# Peripherals.net
KiCad netlist of a schematic drawn in Altium Designer
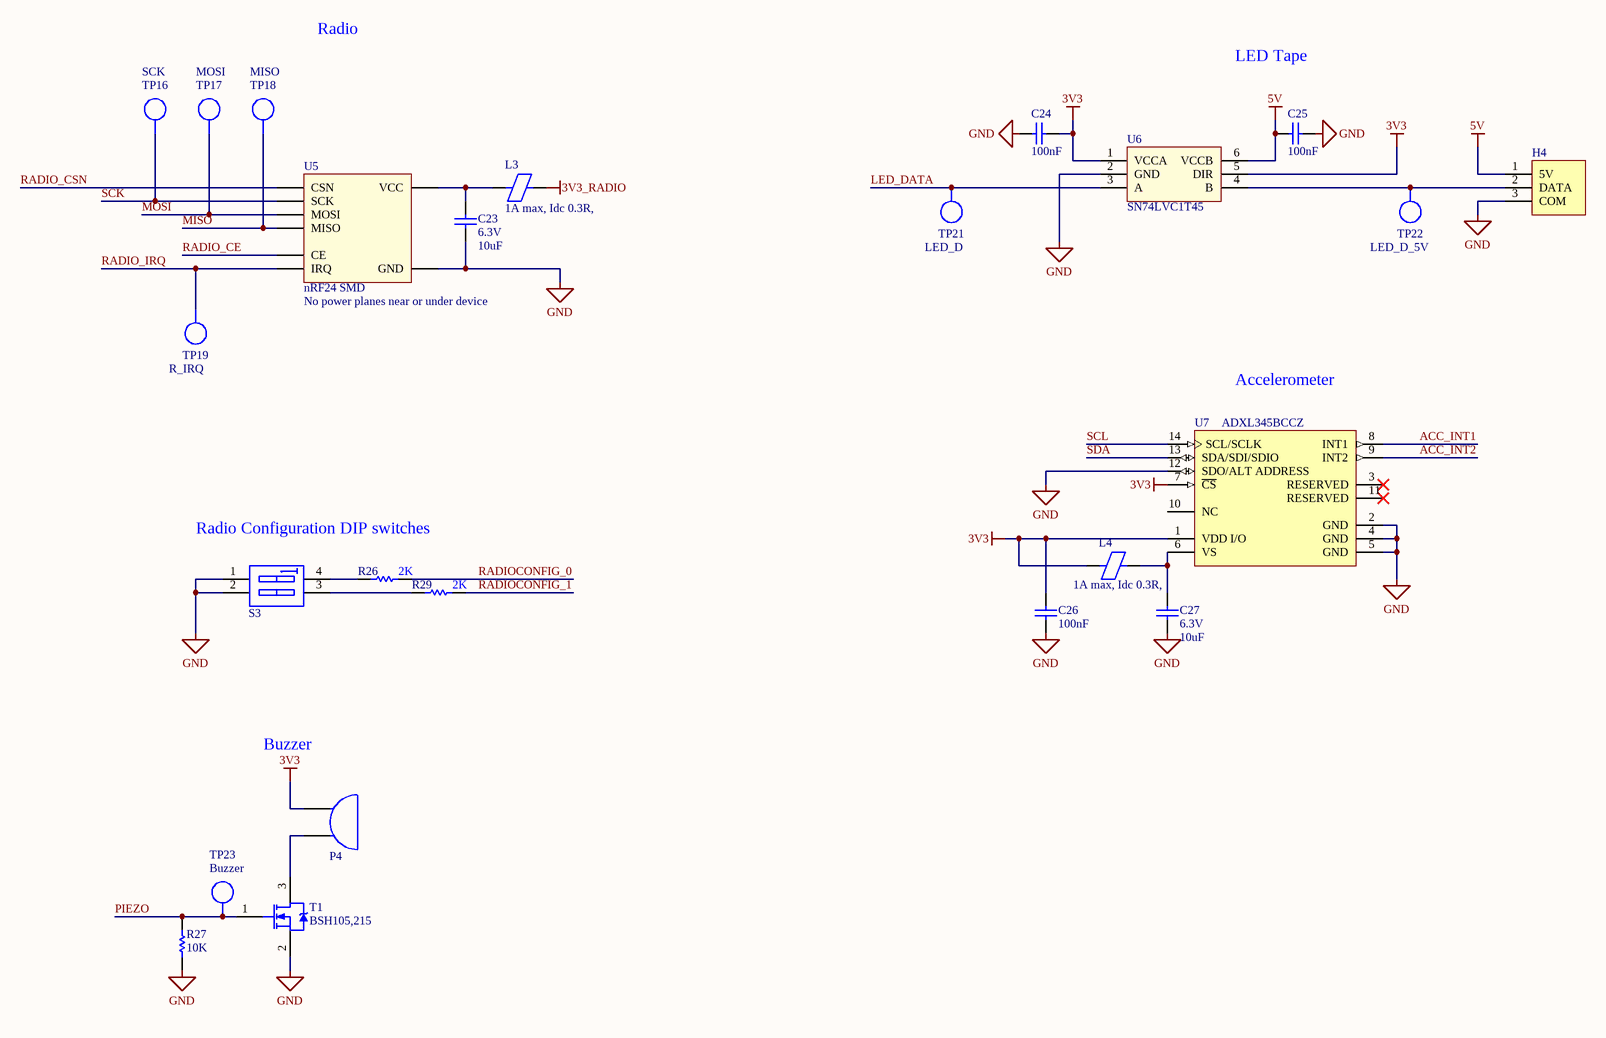
[diagram p0: Peripherals.SchDoc]

(export (version "E")
  (design (tool "Eeschema 10.0.6"))
  (components
    (comp (ref "C23")
      (value "10uF")
      (footprint "CAPC1608L")
      (description "CAP CER 10UF X5R +-20% 6V3 0603")
      (fields (field (name "VOLTAGE - RATED") "6.3V"))
      (libsource (lib "ECE_ComponentsAD23") (part "CC_10uF_0603"))
    )
    (comp (ref "C24")
      (value "100nF")
      (footprint "CAPC1608L")
      (description "CAP CER 100nF X7R +-10% 50V 0603")
      (libsource (lib "ECE_ComponentsAD23") (part "CC_100nF_0603"))
    )
    (comp (ref "C25")
      (value "100nF")
      (footprint "CAPC1608L")
      (description "CAP CER 100nF X7R +-10% 50V 0603")
      (libsource (lib "ECE_ComponentsAD23") (part "CC_100nF_0603"))
    )
    (comp (ref "C26")
      (value "100nF")
      (footprint "CAPC1608L")
      (description "CAP CER 100nF X7R +-10% 50V 0603")
      (libsource (lib "ECE_ComponentsAD23") (part "CC_100nF_0603"))
    )
    (comp (ref "C27")
      (value "10uF")
      (footprint "CAPC1608L")
      (description "CAP CER 10UF X5R +-20% 6V3 0603")
      (fields (field (name "VOLTAGE - RATED") "6.3V"))
      (libsource (lib "ECE_ComponentsAD23") (part "CC_10uF_0603"))
    )
    (comp (ref "H4")
      (value "3 Pin Molex KK Hdr")
      (footprint "MOLEX_KK_3_HDR")
      (description "CONN HEADER 3POS 2.54mm VERT_Thru Hole")
      (fields (field (name "MANUFACTURER") "Molex"))
      (libsource (lib "ENCE461AD23") (part "LED_Strip_Header"))
    )
    (comp (ref "L3")
      (value "1A max, Idc 0.3R,")
      (footprint "INDC3216L")
      (description "Ferrite Bead, Rdc 0.3R, Z100MHZ 600R, Imax 1A, SMD 1206")
      (fields
        (field (name "MANUFACTURER") "FAIR-RITE")
        (field (name "MANUFACTURER PART NUMBER") "2512066017Y1")
      )
      (libsource (lib "ECE_ComponentsAD23") (part "IN_Ferrite-Bead"))
    )
    (comp (ref "L4")
      (value "1A max, Idc 0.3R,")
      (footprint "INDC3216L")
      (description "Ferrite Bead, Rdc 0.3R, Z100MHZ 600R, Imax 1A, SMD 1206")
      (fields
        (field (name "MANUFACTURER") "FAIR-RITE")
        (field (name "MANUFACTURER PART NUMBER") "2512066017Y1")
      )
      (libsource (lib "ECE_ComponentsAD23") (part "IN_Ferrite-Bead"))
    )
    (comp (ref "P4")
      (value "Piezo Buzzer")
      (footprint "BUZZER")
      (description "TDK - PS1240P02BT - BUZZER, PIEZO, 70DB, 12.2MM")
      (libsource (lib "ENCE461AD23") (part "Piezo Buzzer"))
    )
    (comp (ref "R26")
      (value "2K")
      (footprint "RESC1608L")
      (description "RES 2K OHM 1/10W 5% 0603 SMD")
      (libsource (lib "ECE_ComponentsAD23") (part "RS_2K"))
    )
    (comp (ref "R27")
      (value "10K")
      (footprint "RESC1608L")
      (description "RES 10.0K OHM 1/10W 5% 0603 SMD")
      (libsource (lib "ECE_ComponentsAD23") (part "RS_10K"))
    )
    (comp (ref "R29")
      (value "2K")
      (footprint "RESC1608L")
      (description "RES 2K OHM 1/10W 5% 0603 SMD")
      (libsource (lib "ECE_ComponentsAD23") (part "RS_2K"))
    )
    (comp (ref "S3")
      (value "WS_SW DIP-2")
      (footprint "DIP_SW_2WAY_SMD")
      (description "DIP Switch, 2 Position, SPST SMD")
      (fields
        (field (name "MANUFACTURER") "OMRON ELECTRONIC COMPONENTS")
        (field (name "MANUFACTURER PART NUMBER") "A6SN-2101")
      )
      (libsource (lib "ECE_ComponentsAD23") (part "WS_SW DIP-2"))
    )
    (comp (ref "T1")
      (value "BSH105,215")
      (footprint "SOT23_L")
      (description "MOSFET N-CH 20V 1.05A SOT-23")
      (fields
        (field (name "MANUFACTURER") "NXP Semiconductors")
        (field (name "MANUFACTURER PART NUMBER") "BSH105,215")
      )
      (libsource (lib "ECE_ComponentsAD23") (part "TM_BSH105"))
    )
    (comp (ref "TP16")
      (value "SCK")
      (footprint "TP_1206")
      (description "Test-Point 3.3x1.6x2.1mm SMD")
      (fields
        (field (name "MANUFACTURER") "Harwin Inc")
        (field (name "MANUFACTURER PART NUMBER") "S1751-46R")
      )
      (libsource (lib "ECE_ComponentsAD23") (part "TP_1206"))
    )
    (comp (ref "TP17")
      (value "MOSI")
      (footprint "TP_1206")
      (description "Test-Point 3.3x1.6x2.1mm SMD")
      (fields
        (field (name "MANUFACTURER") "Harwin Inc")
        (field (name "MANUFACTURER PART NUMBER") "S1751-46R")
      )
      (libsource (lib "ECE_ComponentsAD23") (part "TP_1206"))
    )
    (comp (ref "TP18")
      (value "MISO")
      (footprint "TP_1206")
      (description "Test-Point 3.3x1.6x2.1mm SMD")
      (fields
        (field (name "MANUFACTURER") "Harwin Inc")
        (field (name "MANUFACTURER PART NUMBER") "S1751-46R")
      )
      (libsource (lib "ECE_ComponentsAD23") (part "TP_1206"))
    )
    (comp (ref "TP19")
      (value "R_IRQ")
      (footprint "TP_1206")
      (description "Test-Point 3.3x1.6x2.1mm SMD")
      (fields
        (field (name "MANUFACTURER") "Harwin Inc")
        (field (name "MANUFACTURER PART NUMBER") "S1751-46R")
      )
      (libsource (lib "ECE_ComponentsAD23") (part "TP_1206"))
    )
    (comp (ref "TP21")
      (value "LED_D")
      (footprint "TP_1206")
      (description "Test-Point 3.3x1.6x2.1mm SMD")
      (fields
        (field (name "MANUFACTURER") "Harwin Inc")
        (field (name "MANUFACTURER PART NUMBER") "S1751-46R")
      )
      (libsource (lib "ECE_ComponentsAD23") (part "TP_1206"))
    )
    (comp (ref "TP22")
      (value "LED_D_5V")
      (footprint "TP_1206")
      (description "Test-Point 3.3x1.6x2.1mm SMD")
      (fields
        (field (name "MANUFACTURER") "Harwin Inc")
        (field (name "MANUFACTURER PART NUMBER") "S1751-46R")
      )
      (libsource (lib "ECE_ComponentsAD23") (part "TP_1206"))
    )
    (comp (ref "TP23")
      (value "Buzzer")
      (footprint "TP_1206")
      (description "Test-Point 3.3x1.6x2.1mm SMD")
      (fields
        (field (name "MANUFACTURER") "Harwin Inc")
        (field (name "MANUFACTURER PART NUMBER") "S1751-46R")
      )
      (libsource (lib "ECE_ComponentsAD23") (part "TP_1206"))
    )
    (comp (ref "U5")
      (value "nRF24 SMD")
      (footprint "NRF24")
      (description "nRF24 SMD Module")
      (fields (field (name "WARNING") "No power planes near or under device"))
      (libsource (lib "ENCE461AD23") (part "NRF24"))
    )
    (comp (ref "U6")
      (value "SN74LVC1T45")
      (footprint "SOT23-6_N")
      (description "1.8V - 5V level converter")
      (libsource (lib "ENCE461AD23") (part "SN74LVC1T45"))
    )
    (comp (ref "U7")
      (value "ADXL345BCCZ")
      (footprint "ADI-CC-14-1_V")
      (fields (field (name "MANUFACTURER") "Analog Devices"))
      (libsource (lib "ENCE461AD23") (part "ADXL345BCCZ"))
    )
  )
  (nets
    (net (code "1") (name "/ACC_INT1") (class "Default")
      (node (ref "U7") (pin "8") (pinfunction "INT1_8") (pintype "output"))
    )
    (net (code "2") (name "/ACC_INT2") (class "Default")
      (node (ref "U7") (pin "9") (pinfunction "INT2_9") (pintype "output"))
    )
    (net (code "3") (name "/LED_DATA") (class "Default")
      (node (ref "TP21") (pin "1") (pinfunction "1_1") (pintype "passive"))
      (node (ref "U6") (pin "3") (pinfunction "A_3") (pintype "passive"))
    )
    (net (code "4") (name "/MISO") (class "Default")
      (node (ref "TP18") (pin "1") (pinfunction "1_1") (pintype "passive"))
      (node (ref "U5") (pin "7") (pinfunction "MISO_7") (pintype "passive"))
    )
    (net (code "5") (name "/MOSI") (class "Default")
      (node (ref "TP17") (pin "1") (pinfunction "1_1") (pintype "passive"))
      (node (ref "U5") (pin "6") (pinfunction "MOSI_6") (pintype "passive"))
    )
    (net (code "6") (name "/PIEZO") (class "Default")
      (node (ref "R27") (pin "1") (pinfunction "1_1") (pintype "passive"))
      (node (ref "T1") (pin "1") (pinfunction "1_1") (pintype "passive"))
      (node (ref "TP23") (pin "1") (pinfunction "1_1") (pintype "passive"))
    )
    (net (code "7") (name "/RADIOCONFIG_0") (class "Default")
      (node (ref "R26") (pin "2") (pinfunction "2_2") (pintype "passive"))
    )
    (net (code "8") (name "/RADIOCONFIG_1") (class "Default")
      (node (ref "R29") (pin "2") (pinfunction "2_2") (pintype "passive"))
    )
    (net (code "9") (name "/RADIO_CE") (class "Default")
      (node (ref "U5") (pin "3") (pinfunction "CE_3") (pintype "passive"))
    )
    (net (code "10") (name "/RADIO_CSN") (class "Default")
      (node (ref "U5") (pin "4") (pinfunction "CSN_4") (pintype "passive"))
    )
    (net (code "11") (name "/RADIO_IRQ") (class "Default")
      (node (ref "TP19") (pin "1") (pinfunction "1_1") (pintype "passive"))
      (node (ref "U5") (pin "8") (pinfunction "IRQ_8") (pintype "passive"))
    )
    (net (code "12") (name "/SCK") (class "Default")
      (node (ref "TP16") (pin "1") (pinfunction "1_1") (pintype "passive"))
      (node (ref "U5") (pin "5") (pinfunction "SCK_5") (pintype "passive"))
    )
    (net (code "13") (name "/SCL") (class "Default")
      (node (ref "U7") (pin "14") (pinfunction "SCL/SCLK_14") (pintype "input"))
    )
    (net (code "14") (name "/SDA") (class "Default")
      (node (ref "U7") (pin "13") (pinfunction "SDA/SDI/SDIO_13") (pintype "bidirectional"))
    )
    (net (code "15") (name "3V3") (class "Default")
      (node (ref "C24") (pin "2") (pinfunction "2_2") (pintype "passive"))
      (node (ref "C26") (pin "2") (pinfunction "2_2") (pintype "passive"))
      (node (ref "L4") (pin "2") (pinfunction "2_2") (pintype "passive"))
      (node (ref "P4") (pin "1") (pinfunction "1_1") (pintype "passive"))
      (node (ref "U6") (pin "1") (pinfunction "VCCA_1") (pintype "passive"))
      (node (ref "U6") (pin "5") (pinfunction "DIR_5") (pintype "passive"))
      (node (ref "U7") (pin "1") (pinfunction "VDD_I/O_1") (pintype "power_in"))
      (node (ref "U7") (pin "7") (pinfunction "~{CS}_7") (pintype "input"))
    )
    (net (code "16") (name "3V3_RADIO") (class "Default")
      (node (ref "L3") (pin "2") (pinfunction "2_2") (pintype "passive"))
    )
    (net (code "17") (name "5V") (class "Default")
      (node (ref "C25") (pin "2") (pinfunction "2_2") (pintype "passive"))
      (node (ref "H4") (pin "1") (pinfunction "5V_1") (pintype "passive"))
      (node (ref "U6") (pin "6") (pinfunction "VCCB_6") (pintype "passive"))
    )
    (net (code "18") (name "GND") (class "Default")
      (node (ref "C23") (pin "1") (pinfunction "1_1") (pintype "passive"))
      (node (ref "C24") (pin "1") (pinfunction "1_1") (pintype "passive"))
      (node (ref "C25") (pin "1") (pinfunction "1_1") (pintype "passive"))
      (node (ref "C26") (pin "1") (pinfunction "1_1") (pintype "passive"))
      (node (ref "C27") (pin "1") (pinfunction "1_1") (pintype "passive"))
      (node (ref "H4") (pin "3") (pinfunction "COM_3") (pintype "passive"))
      (node (ref "R27") (pin "2") (pinfunction "2_2") (pintype "passive"))
      (node (ref "S3") (pin "1") (pinfunction "A1_1") (pintype "passive"))
      (node (ref "S3") (pin "2") (pinfunction "A2_2") (pintype "passive"))
      (node (ref "T1") (pin "2") (pinfunction "2_2") (pintype "passive"))
      (node (ref "U5") (pin "2") (pinfunction "GND_2") (pintype "passive"))
      (node (ref "U6") (pin "2") (pinfunction "GND_2") (pintype "passive"))
      (node (ref "U7") (pin "12") (pinfunction "SDO/ALT_ADDRESS_12") (pintype "bidirectional"))
      (node (ref "U7") (pin "2") (pinfunction "GND_2") (pintype "power_in"))
      (node (ref "U7") (pin "4") (pinfunction "GND_4") (pintype "power_in"))
      (node (ref "U7") (pin "5") (pinfunction "GND_5") (pintype "power_in"))
    )
    (net (code "19") (name "Net-(H4-DATA)") (class "Default")
      (node (ref "H4") (pin "2") (pinfunction "DATA_2") (pintype "passive"))
      (node (ref "TP22") (pin "1") (pinfunction "1_1") (pintype "passive"))
      (node (ref "U6") (pin "4") (pinfunction "B_4") (pintype "passive"))
    )
    (net (code "20") (name "Net-(P4-Pad2)") (class "Default")
      (node (ref "P4") (pin "2") (pinfunction "2_2") (pintype "passive"))
      (node (ref "T1") (pin "3") (pinfunction "3_3") (pintype "passive"))
    )
    (net (code "21") (name "Net-(S3-B1)") (class "Default")
      (node (ref "R26") (pin "1") (pinfunction "1_1") (pintype "passive"))
      (node (ref "S3") (pin "4") (pinfunction "B1_4") (pintype "passive"))
    )
    (net (code "22") (name "Net-(S3-B2)") (class "Default")
      (node (ref "R29") (pin "1") (pinfunction "1_1") (pintype "passive"))
      (node (ref "S3") (pin "3") (pinfunction "B2_3") (pintype "passive"))
    )
    (net (code "23") (name "Net-(U5-VCC)") (class "Default")
      (node (ref "C23") (pin "2") (pinfunction "2_2") (pintype "passive"))
      (node (ref "L3") (pin "1") (pinfunction "1_1") (pintype "passive"))
      (node (ref "U5") (pin "1") (pinfunction "VCC_1") (pintype "passive"))
    )
    (net (code "24") (name "Net-(U7-VS)") (class "Default")
      (node (ref "C27") (pin "2") (pinfunction "2_2") (pintype "passive"))
      (node (ref "L4") (pin "1") (pinfunction "1_1") (pintype "passive"))
      (node (ref "U7") (pin "6") (pinfunction "VS_6") (pintype "power_in"))
    )
    (net (code "25") (name "unconnected-(U7-NC-Pad10)") (class "Default")
      (node (ref "U7") (pin "10") (pinfunction "NC_10") (pintype "passive"))
    )
    (net (code "26") (name "unconnected-(U7-RESERVED-Pad3)") (class "Default")
      (node (ref "U7") (pin "3") (pinfunction "RESERVED_3") (pintype "passive+no_connect"))
    )
    (net (code "27") (name "unconnected-(U7-RESERVED-Pad11)") (class "Default")
      (node (ref "U7") (pin "11") (pinfunction "RESERVED_11") (pintype "passive+no_connect"))
    )
  )
)
